# output.net
KiCad netlist of a schematic drawn in EAGLE
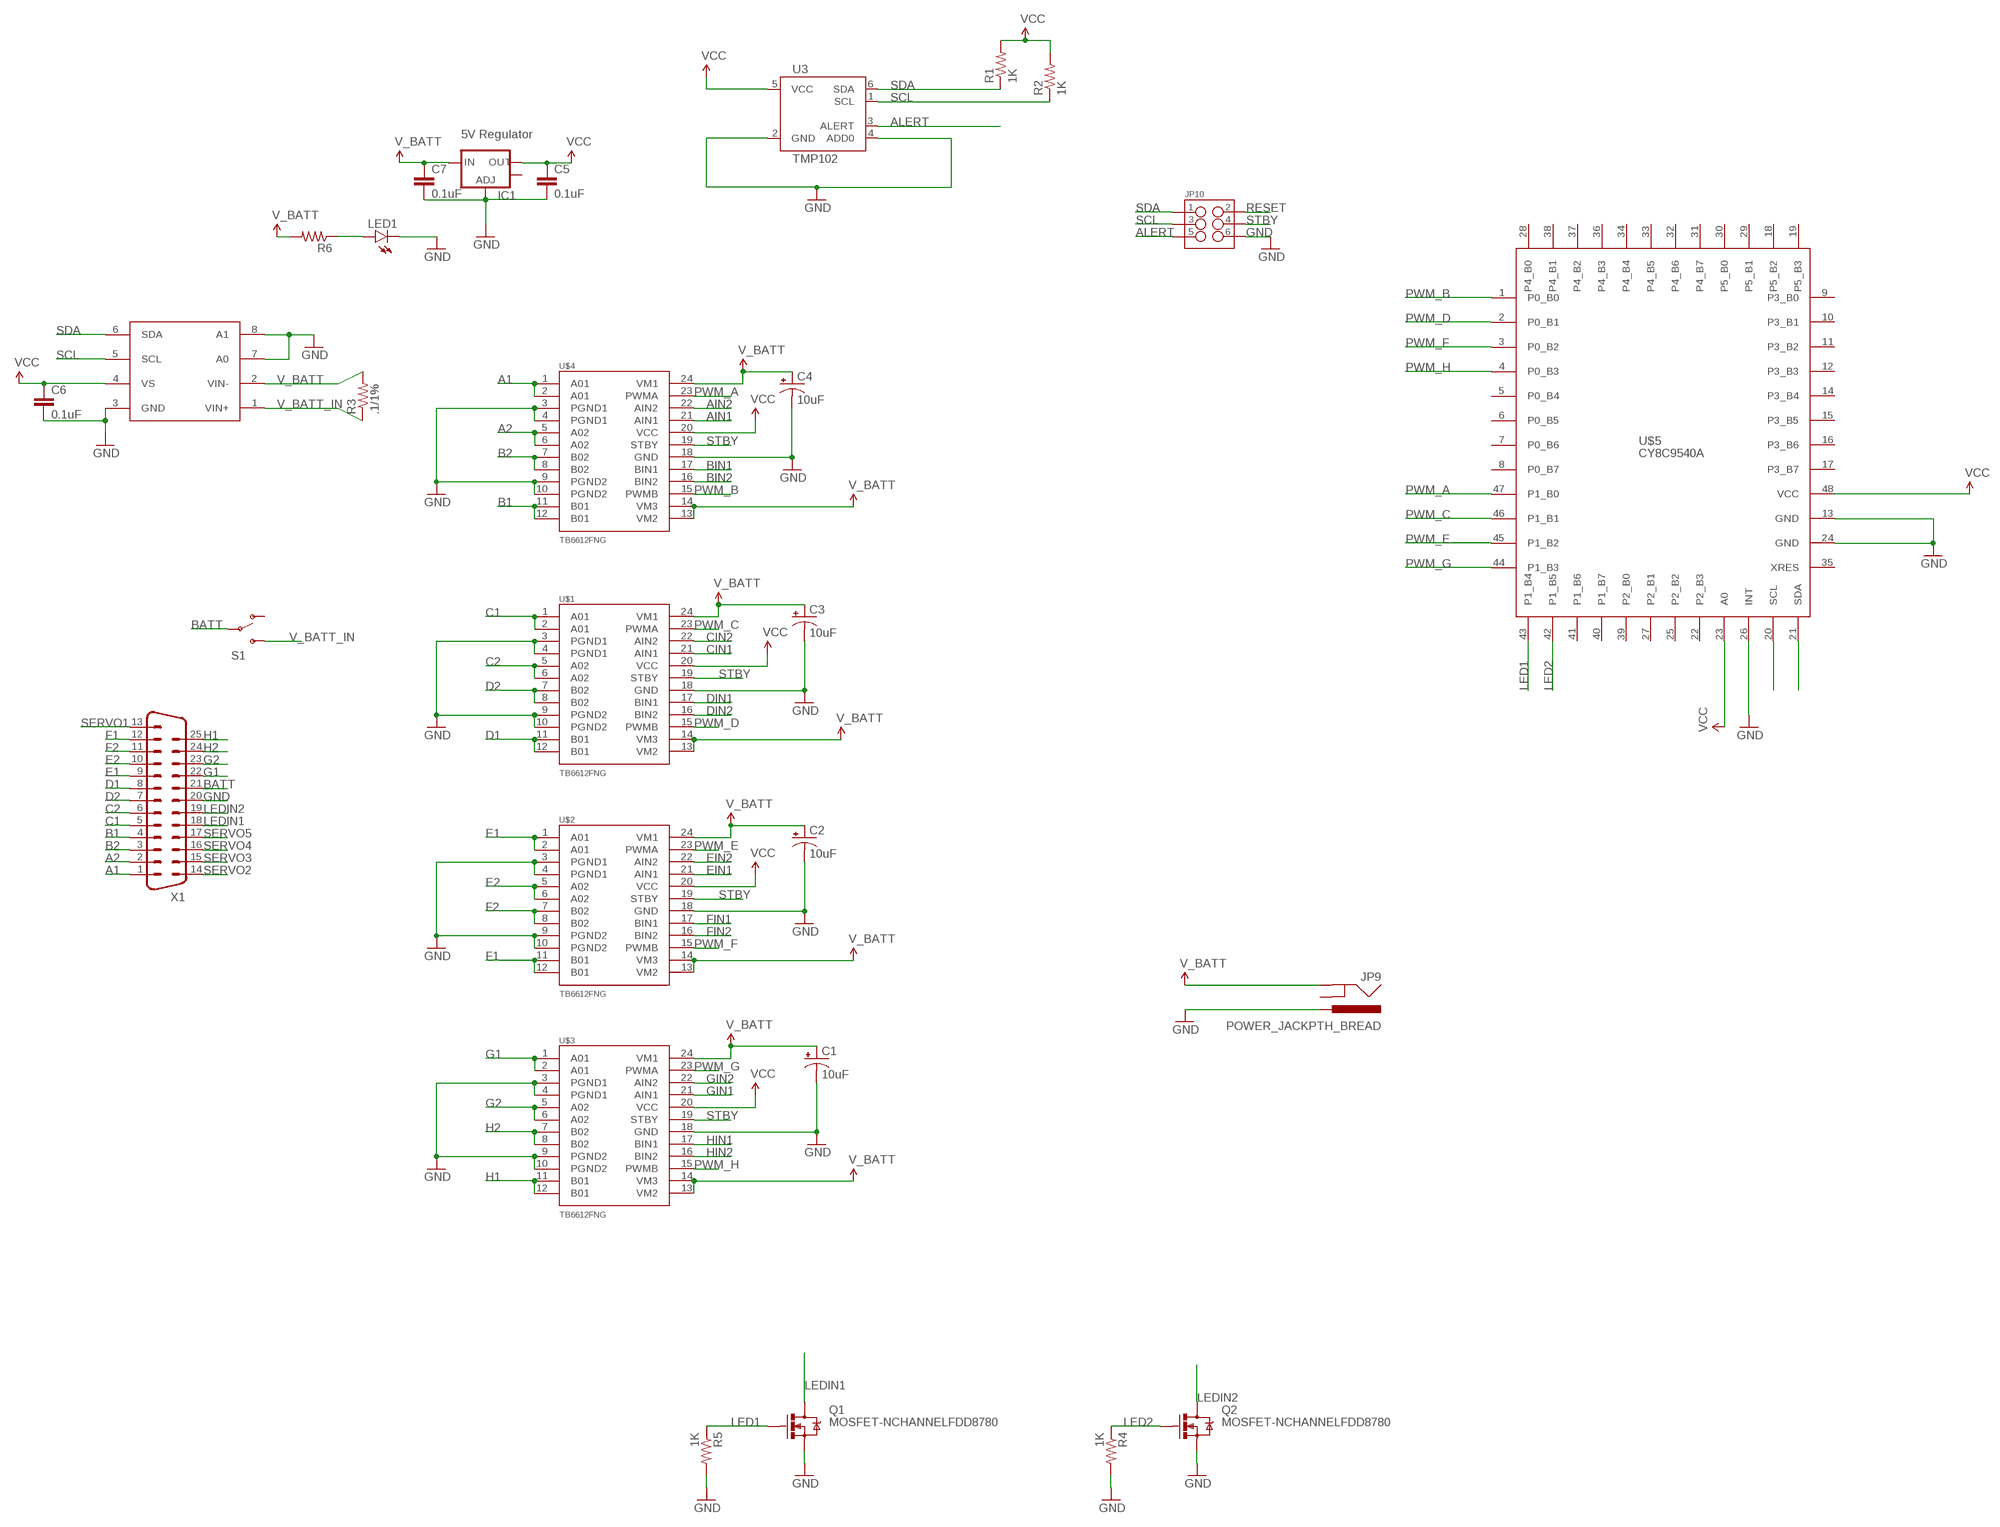
[diagram p0: schematic, sheet 1]

(export (version "E")
  (design (tool "Eeschema 10.0.6"))
  (components
    (comp (ref "C1")
      (value "10uF")
      (footprint "eagle-import:EIA3528")
      (libsource (lib "eagle-import") (part "10UF-20V-10%(TANT)"))
    )
    (comp (ref "C2")
      (value "10uF")
      (footprint "eagle-import:EIA3528")
      (libsource (lib "eagle-import") (part "10UF-20V-10%(TANT)"))
    )
    (comp (ref "C3")
      (value "10uF")
      (footprint "eagle-import:EIA3528")
      (libsource (lib "eagle-import") (part "10UF-20V-10%(TANT)"))
    )
    (comp (ref "C4")
      (value "10uF")
      (footprint "eagle-import:EIA3528")
      (libsource (lib "eagle-import") (part "10UF-20V-10%(TANT)"))
    )
    (comp (ref "C5")
      (value "0.1uF")
      (footprint "eagle-import:0603-CAP")
      (libsource (lib "eagle-import") (part "0.1UF-25V-5%(0603)"))
    )
    (comp (ref "C6")
      (value "0.1uF")
      (footprint "eagle-import:0603-CAP")
      (libsource (lib "eagle-import") (part "0.1UF-25V-5%(0603)"))
    )
    (comp (ref "C7")
      (value "0.1uF")
      (footprint "eagle-import:0603-CAP")
      (libsource (lib "eagle-import") (part "0.1UF-25V-5%(0603)"))
    )
    (comp (ref "IC1")
      (value "V_REG_LM1117SOT223")
      (footprint "eagle-import:SOT223")
      (libsource (lib "eagle-import") (part "V_REG_LM1117SOT223"))
    )
    (comp (ref "JP9")
      (value "POWER_JACKPTH_BREAD")
      (footprint "eagle-import:POWER_JACK_PTH_BREAD")
      (libsource (lib "eagle-import") (part "POWER_JACKPTH_BREAD"))
    )
    (comp (ref "JP10")
      (value "M03X2SHROUD")
      (footprint "eagle-import:2X3-SHROUDED")
      (libsource (lib "eagle-import") (part "M03X2SHROUD"))
    )
    (comp (ref "LED1")
      (value "LED0603")
      (footprint "eagle-import:LED-0603")
      (libsource (lib "eagle-import") (part "LED0603"))
    )
    (comp (ref "Q1")
      (value "MOSFET-NCHANNELFDD8780")
      (footprint "eagle-import:DPAK")
      (libsource (lib "eagle-import") (part "MOSFET-NCHANNELFDD8780"))
    )
    (comp (ref "Q2")
      (value "MOSFET-NCHANNELFDD8780")
      (footprint "eagle-import:DPAK")
      (libsource (lib "eagle-import") (part "MOSFET-NCHANNELFDD8780"))
    )
    (comp (ref "R1")
      (value "1K")
      (footprint "eagle-import:0603-RES")
      (libsource (lib "eagle-import") (part "1KOHM-1/10W-1%(0603)"))
    )
    (comp (ref "R2")
      (value "1K")
      (footprint "eagle-import:0603-RES")
      (libsource (lib "eagle-import") (part "1KOHM-1/10W-1%(0603)"))
    )
    (comp (ref "R3")
      (value ".1/1%")
      (footprint "eagle-import:R2512")
      (libsource (lib "eagle-import") (part "RESISTOR2512"))
    )
    (comp (ref "R4")
      (value "1K")
      (footprint "eagle-import:0603-RES")
      (libsource (lib "eagle-import") (part "1KOHM-1/10W-1%(0603)"))
    )
    (comp (ref "R5")
      (value "1K")
      (footprint "eagle-import:0603-RES")
      (libsource (lib "eagle-import") (part "1KOHM-1/10W-1%(0603)"))
    )
    (comp (ref "R6")
      (value "RESISTOR0603-RES")
      (footprint "eagle-import:0603-RES")
      (libsource (lib "eagle-import") (part "RESISTOR0603-RES"))
    )
    (comp (ref "S1")
      (value "SWITCH-SPDTKIT")
      (footprint "eagle-import:SWITCH-SPDT_KIT")
      (fields (field (name "PARTNO") "EG1218"))
      (libsource (lib "eagle-import") (part "SWITCH-SPDTKIT"))
    )
    (comp (ref "U$1")
      (value "TB6612FNG")
      (footprint "eagle-import:SSOP24")
      (libsource (lib "eagle-import") (part "TB6612FNG"))
    )
    (comp (ref "U$2")
      (value "TB6612FNG")
      (footprint "eagle-import:SSOP24")
      (libsource (lib "eagle-import") (part "TB6612FNG"))
    )
    (comp (ref "U$3")
      (value "TB6612FNG")
      (footprint "eagle-import:SSOP24")
      (libsource (lib "eagle-import") (part "TB6612FNG"))
    )
    (comp (ref "U$4")
      (value "TB6612FNG")
      (footprint "eagle-import:SSOP24")
      (libsource (lib "eagle-import") (part "TB6612FNG"))
    )
    (comp (ref "U$5")
      (value "CY8C9540A")
      (footprint "eagle-import:48-SSOP-CY")
      (libsource (lib "eagle-import") (part "CY8C9540A"))
    )
    (comp (ref "U$6")
      (value "INA219")
      (footprint "eagle-import:SOT23-8")
      (libsource (lib "eagle-import") (part "INA219"))
    )
    (comp (ref "U3")
      (value "TMP102")
      (footprint "eagle-import:SOT563")
      (libsource (lib "eagle-import") (part "TMP102"))
    )
    (comp (ref "X1")
      (value "DB25D")
      (footprint "eagle-import:M25D")
      (libsource (lib "eagle-import") (part "DB25D"))
    )
  )
  (nets
    (net (code "1") (name "/A1") (class "Default")
      (node (ref "U$4") (pin "1") (pinfunction "A01_1") (pintype "bidirectional"))
      (node (ref "U$4") (pin "2") (pinfunction "A01_2") (pintype "bidirectional"))
      (node (ref "X1") (pin "1") (pinfunction "1_1") (pintype "passive"))
    )
    (net (code "2") (name "/A2") (class "Default")
      (node (ref "U$4") (pin "5") (pinfunction "A02_5") (pintype "bidirectional"))
      (node (ref "U$4") (pin "6") (pinfunction "A02_6") (pintype "bidirectional"))
      (node (ref "X1") (pin "2") (pinfunction "2_2") (pintype "passive"))
    )
    (net (code "3") (name "/AIN1") (class "Default")
      (node (ref "U$4") (pin "21") (pinfunction "AIN1_21") (pintype "bidirectional"))
    )
    (net (code "4") (name "/AIN2") (class "Default")
      (node (ref "U$4") (pin "22") (pinfunction "AIN2_22") (pintype "bidirectional"))
    )
    (net (code "5") (name "/ALERT") (class "Default")
      (node (ref "JP10") (pin "5") (pinfunction "5_5") (pintype "bidirectional"))
      (node (ref "U3") (pin "3") (pinfunction "ALERT_3") (pintype "bidirectional"))
    )
    (net (code "6") (name "/B1") (class "Default")
      (node (ref "U$4") (pin "11") (pinfunction "B01_11") (pintype "bidirectional"))
      (node (ref "U$4") (pin "12") (pinfunction "B01_12") (pintype "bidirectional"))
      (node (ref "X1") (pin "4") (pinfunction "4_4") (pintype "passive"))
    )
    (net (code "7") (name "/B2") (class "Default")
      (node (ref "U$4") (pin "7") (pinfunction "B02_7") (pintype "bidirectional"))
      (node (ref "U$4") (pin "8") (pinfunction "B02_8") (pintype "bidirectional"))
      (node (ref "X1") (pin "3") (pinfunction "3_3") (pintype "passive"))
    )
    (net (code "8") (name "/BATT") (class "Default")
      (node (ref "S1") (pin "2") (pinfunction "P_2") (pintype "passive"))
      (node (ref "X1") (pin "21") (pinfunction "21_21") (pintype "passive"))
    )
    (net (code "9") (name "/BIN1") (class "Default")
      (node (ref "U$4") (pin "17") (pinfunction "BIN1_17") (pintype "bidirectional"))
    )
    (net (code "10") (name "/BIN2") (class "Default")
      (node (ref "U$4") (pin "16") (pinfunction "BIN2_16") (pintype "bidirectional"))
    )
    (net (code "11") (name "/C1") (class "Default")
      (node (ref "U$1") (pin "1") (pinfunction "A01_1") (pintype "bidirectional"))
      (node (ref "U$1") (pin "2") (pinfunction "A01_2") (pintype "bidirectional"))
      (node (ref "X1") (pin "5") (pinfunction "5_5") (pintype "passive"))
    )
    (net (code "12") (name "/C2") (class "Default")
      (node (ref "U$1") (pin "5") (pinfunction "A02_5") (pintype "bidirectional"))
      (node (ref "U$1") (pin "6") (pinfunction "A02_6") (pintype "bidirectional"))
      (node (ref "X1") (pin "6") (pinfunction "6_6") (pintype "passive"))
    )
    (net (code "13") (name "/CIN1") (class "Default")
      (node (ref "U$1") (pin "21") (pinfunction "AIN1_21") (pintype "bidirectional"))
    )
    (net (code "14") (name "/CIN2") (class "Default")
      (node (ref "U$1") (pin "22") (pinfunction "AIN2_22") (pintype "bidirectional"))
    )
    (net (code "15") (name "/D1") (class "Default")
      (node (ref "U$1") (pin "11") (pinfunction "B01_11") (pintype "bidirectional"))
      (node (ref "U$1") (pin "12") (pinfunction "B01_12") (pintype "bidirectional"))
      (node (ref "X1") (pin "8") (pinfunction "8_8") (pintype "passive"))
    )
    (net (code "16") (name "/D2") (class "Default")
      (node (ref "U$1") (pin "7") (pinfunction "B02_7") (pintype "bidirectional"))
      (node (ref "U$1") (pin "8") (pinfunction "B02_8") (pintype "bidirectional"))
      (node (ref "X1") (pin "7") (pinfunction "7_7") (pintype "passive"))
    )
    (net (code "17") (name "/DIN1") (class "Default")
      (node (ref "U$1") (pin "17") (pinfunction "BIN1_17") (pintype "bidirectional"))
    )
    (net (code "18") (name "/DIN2") (class "Default")
      (node (ref "U$1") (pin "16") (pinfunction "BIN2_16") (pintype "bidirectional"))
    )
    (net (code "19") (name "/E1") (class "Default")
      (node (ref "U$2") (pin "1") (pinfunction "A01_1") (pintype "bidirectional"))
      (node (ref "U$2") (pin "2") (pinfunction "A01_2") (pintype "bidirectional"))
      (node (ref "X1") (pin "9") (pinfunction "9_9") (pintype "passive"))
    )
    (net (code "20") (name "/E2") (class "Default")
      (node (ref "U$2") (pin "5") (pinfunction "A02_5") (pintype "bidirectional"))
      (node (ref "U$2") (pin "6") (pinfunction "A02_6") (pintype "bidirectional"))
      (node (ref "X1") (pin "10") (pinfunction "10_10") (pintype "passive"))
    )
    (net (code "21") (name "/EIN1") (class "Default")
      (node (ref "U$2") (pin "21") (pinfunction "AIN1_21") (pintype "bidirectional"))
    )
    (net (code "22") (name "/EIN2") (class "Default")
      (node (ref "U$2") (pin "22") (pinfunction "AIN2_22") (pintype "bidirectional"))
    )
    (net (code "23") (name "/F1") (class "Default")
      (node (ref "U$2") (pin "11") (pinfunction "B01_11") (pintype "bidirectional"))
      (node (ref "U$2") (pin "12") (pinfunction "B01_12") (pintype "bidirectional"))
      (node (ref "X1") (pin "12") (pinfunction "12_12") (pintype "passive"))
    )
    (net (code "24") (name "/F2") (class "Default")
      (node (ref "U$2") (pin "7") (pinfunction "B02_7") (pintype "bidirectional"))
      (node (ref "U$2") (pin "8") (pinfunction "B02_8") (pintype "bidirectional"))
      (node (ref "X1") (pin "11") (pinfunction "11_11") (pintype "passive"))
    )
    (net (code "25") (name "/FIN1") (class "Default")
      (node (ref "U$2") (pin "17") (pinfunction "BIN1_17") (pintype "bidirectional"))
    )
    (net (code "26") (name "/FIN2") (class "Default")
      (node (ref "U$2") (pin "16") (pinfunction "BIN2_16") (pintype "bidirectional"))
    )
    (net (code "27") (name "/G1") (class "Default")
      (node (ref "U$3") (pin "1") (pinfunction "A01_1") (pintype "bidirectional"))
      (node (ref "U$3") (pin "2") (pinfunction "A01_2") (pintype "bidirectional"))
      (node (ref "X1") (pin "22") (pinfunction "22_22") (pintype "passive"))
    )
    (net (code "28") (name "/G2") (class "Default")
      (node (ref "U$3") (pin "5") (pinfunction "A02_5") (pintype "bidirectional"))
      (node (ref "U$3") (pin "6") (pinfunction "A02_6") (pintype "bidirectional"))
      (node (ref "X1") (pin "23") (pinfunction "23_23") (pintype "passive"))
    )
    (net (code "29") (name "/GIN1") (class "Default")
      (node (ref "U$3") (pin "21") (pinfunction "AIN1_21") (pintype "bidirectional"))
    )
    (net (code "30") (name "/GIN2") (class "Default")
      (node (ref "U$3") (pin "22") (pinfunction "AIN2_22") (pintype "bidirectional"))
    )
    (net (code "31") (name "/H1") (class "Default")
      (node (ref "U$3") (pin "11") (pinfunction "B01_11") (pintype "bidirectional"))
      (node (ref "U$3") (pin "12") (pinfunction "B01_12") (pintype "bidirectional"))
      (node (ref "X1") (pin "25") (pinfunction "25_25") (pintype "passive"))
    )
    (net (code "32") (name "/H2") (class "Default")
      (node (ref "U$3") (pin "7") (pinfunction "B02_7") (pintype "bidirectional"))
      (node (ref "U$3") (pin "8") (pinfunction "B02_8") (pintype "bidirectional"))
      (node (ref "X1") (pin "24") (pinfunction "24_24") (pintype "passive"))
    )
    (net (code "33") (name "/HIN1") (class "Default")
      (node (ref "U$3") (pin "17") (pinfunction "BIN1_17") (pintype "bidirectional"))
    )
    (net (code "34") (name "/HIN2") (class "Default")
      (node (ref "U$3") (pin "16") (pinfunction "BIN2_16") (pintype "bidirectional"))
    )
    (net (code "35") (name "/LED1") (class "Default")
      (node (ref "Q1") (pin "1") (pinfunction "G_1") (pintype "passive"))
      (node (ref "R5") (pin "1") (pinfunction "1_1") (pintype "passive"))
      (node (ref "U$5") (pin "43") (pinfunction "P1_B4_43") (pintype "bidirectional"))
    )
    (net (code "36") (name "/LED2") (class "Default")
      (node (ref "Q2") (pin "1") (pinfunction "G_1") (pintype "passive"))
      (node (ref "R4") (pin "1") (pinfunction "1_1") (pintype "passive"))
      (node (ref "U$5") (pin "42") (pinfunction "P1_B5_42") (pintype "bidirectional"))
    )
    (net (code "37") (name "/LEDIN1") (class "Default")
      (node (ref "Q1") (pin "4") (pinfunction "D_4") (pintype "passive"))
      (node (ref "X1") (pin "18") (pinfunction "18_18") (pintype "passive"))
    )
    (net (code "38") (name "/LEDIN2") (class "Default")
      (node (ref "Q2") (pin "4") (pinfunction "D_4") (pintype "passive"))
      (node (ref "X1") (pin "19") (pinfunction "19_19") (pintype "passive"))
    )
    (net (code "39") (name "/PWM_A") (class "Default")
      (node (ref "U$4") (pin "23") (pinfunction "PWMA_23") (pintype "bidirectional"))
      (node (ref "U$5") (pin "47") (pinfunction "P1_B0_47") (pintype "bidirectional"))
    )
    (net (code "40") (name "/PWM_B") (class "Default")
      (node (ref "U$4") (pin "15") (pinfunction "PWMB_15") (pintype "bidirectional"))
      (node (ref "U$5") (pin "1") (pinfunction "P0_B0_1") (pintype "bidirectional"))
    )
    (net (code "41") (name "/PWM_C") (class "Default")
      (node (ref "U$1") (pin "23") (pinfunction "PWMA_23") (pintype "bidirectional"))
      (node (ref "U$5") (pin "46") (pinfunction "P1_B1_46") (pintype "bidirectional"))
    )
    (net (code "42") (name "/PWM_D") (class "Default")
      (node (ref "U$1") (pin "15") (pinfunction "PWMB_15") (pintype "bidirectional"))
      (node (ref "U$5") (pin "2") (pinfunction "P0_B1_2") (pintype "bidirectional"))
    )
    (net (code "43") (name "/PWM_E") (class "Default")
      (node (ref "U$2") (pin "23") (pinfunction "PWMA_23") (pintype "bidirectional"))
      (node (ref "U$5") (pin "45") (pinfunction "P1_B2_45") (pintype "bidirectional"))
    )
    (net (code "44") (name "/PWM_F") (class "Default")
      (node (ref "U$2") (pin "15") (pinfunction "PWMB_15") (pintype "bidirectional"))
      (node (ref "U$5") (pin "3") (pinfunction "P0_B2_3") (pintype "bidirectional"))
    )
    (net (code "45") (name "/PWM_G") (class "Default")
      (node (ref "U$3") (pin "23") (pinfunction "PWMA_23") (pintype "bidirectional"))
      (node (ref "U$5") (pin "44") (pinfunction "P1_B3_44") (pintype "bidirectional"))
    )
    (net (code "46") (name "/PWM_H") (class "Default")
      (node (ref "U$3") (pin "15") (pinfunction "PWMB_15") (pintype "bidirectional"))
      (node (ref "U$5") (pin "4") (pinfunction "P0_B3_4") (pintype "bidirectional"))
    )
    (net (code "47") (name "/RESET") (class "Default")
      (node (ref "JP10") (pin "2") (pinfunction "2_2") (pintype "bidirectional"))
    )
    (net (code "48") (name "/SCL") (class "Default")
      (node (ref "JP10") (pin "3") (pinfunction "3_3") (pintype "bidirectional"))
      (node (ref "R2") (pin "1") (pinfunction "1_1") (pintype "passive"))
      (node (ref "U$5") (pin "20") (pinfunction "SCL_20") (pintype "bidirectional"))
      (node (ref "U$6") (pin "5") (pinfunction "SCL_5") (pintype "bidirectional"))
      (node (ref "U3") (pin "1") (pinfunction "SCL_1") (pintype "bidirectional"))
    )
    (net (code "49") (name "/SDA") (class "Default")
      (node (ref "JP10") (pin "1") (pinfunction "1_1") (pintype "bidirectional"))
      (node (ref "R1") (pin "1") (pinfunction "1_1") (pintype "passive"))
      (node (ref "U$5") (pin "21") (pinfunction "SDA_21") (pintype "bidirectional"))
      (node (ref "U$6") (pin "6") (pinfunction "SDA_6") (pintype "bidirectional"))
      (node (ref "U3") (pin "6") (pinfunction "SDA_6") (pintype "bidirectional"))
    )
    (net (code "50") (name "/SERVO1") (class "Default")
      (node (ref "X1") (pin "13") (pinfunction "13_13") (pintype "passive"))
    )
    (net (code "51") (name "/SERVO2") (class "Default")
      (node (ref "X1") (pin "14") (pinfunction "14_14") (pintype "passive"))
    )
    (net (code "52") (name "/SERVO3") (class "Default")
      (node (ref "X1") (pin "15") (pinfunction "15_15") (pintype "passive"))
    )
    (net (code "53") (name "/SERVO4") (class "Default")
      (node (ref "X1") (pin "16") (pinfunction "16_16") (pintype "passive"))
    )
    (net (code "54") (name "/SERVO5") (class "Default")
      (node (ref "X1") (pin "17") (pinfunction "17_17") (pintype "passive"))
    )
    (net (code "55") (name "/STBY") (class "Default")
      (node (ref "JP10") (pin "4") (pinfunction "4_4") (pintype "bidirectional"))
      (node (ref "U$1") (pin "19") (pinfunction "STBY_19") (pintype "bidirectional"))
      (node (ref "U$2") (pin "19") (pinfunction "STBY_19") (pintype "bidirectional"))
      (node (ref "U$3") (pin "19") (pinfunction "STBY_19") (pintype "bidirectional"))
      (node (ref "U$4") (pin "19") (pinfunction "STBY_19") (pintype "bidirectional"))
    )
    (net (code "56") (name "/V_BATT_IN") (class "Default")
      (node (ref "R3") (pin "1") (pinfunction "1_1") (pintype "passive"))
      (node (ref "S1") (pin "3") (pinfunction "S_3") (pintype "passive"))
      (node (ref "U$6") (pin "1") (pinfunction "VIN+_1") (pintype "bidirectional"))
    )
    (net (code "57") (name "GND") (class "Default")
      (node (ref "C1") (pin "C") (pinfunction "-_C") (pintype "passive"))
      (node (ref "C2") (pin "C") (pinfunction "-_C") (pintype "passive"))
      (node (ref "C3") (pin "C") (pinfunction "-_C") (pintype "passive"))
      (node (ref "C4") (pin "C") (pinfunction "-_C") (pintype "passive"))
      (node (ref "C5") (pin "2") (pinfunction "2_2") (pintype "passive"))
      (node (ref "C6") (pin "2") (pinfunction "2_2") (pintype "passive"))
      (node (ref "C7") (pin "2") (pinfunction "2_2") (pintype "passive"))
      (node (ref "IC1") (pin "1") (pinfunction "ADJ_1") (pintype "input"))
      (node (ref "JP10") (pin "6") (pinfunction "6_6") (pintype "bidirectional"))
      (node (ref "JP9") (pin "PWR") (pinfunction "PWR_PWR") (pintype "bidirectional"))
      (node (ref "LED1") (pin "C") (pinfunction "C_C") (pintype "passive"))
      (node (ref "Q1") (pin "3") (pinfunction "S_3") (pintype "passive"))
      (node (ref "Q2") (pin "3") (pinfunction "S_3") (pintype "passive"))
      (node (ref "R4") (pin "2") (pinfunction "2_2") (pintype "passive"))
      (node (ref "R5") (pin "2") (pinfunction "2_2") (pintype "passive"))
      (node (ref "U$1") (pin "10") (pinfunction "PGND2_10") (pintype "bidirectional"))
      (node (ref "U$1") (pin "18") (pinfunction "GND_18") (pintype "bidirectional"))
      (node (ref "U$1") (pin "3") (pinfunction "PGND1_3") (pintype "bidirectional"))
      (node (ref "U$1") (pin "4") (pinfunction "PGND1_4") (pintype "bidirectional"))
      (node (ref "U$1") (pin "9") (pinfunction "PGND2_9") (pintype "bidirectional"))
      (node (ref "U$2") (pin "10") (pinfunction "PGND2_10") (pintype "bidirectional"))
      (node (ref "U$2") (pin "18") (pinfunction "GND_18") (pintype "bidirectional"))
      (node (ref "U$2") (pin "3") (pinfunction "PGND1_3") (pintype "bidirectional"))
      (node (ref "U$2") (pin "4") (pinfunction "PGND1_4") (pintype "bidirectional"))
      (node (ref "U$2") (pin "9") (pinfunction "PGND2_9") (pintype "bidirectional"))
      (node (ref "U$3") (pin "10") (pinfunction "PGND2_10") (pintype "bidirectional"))
      (node (ref "U$3") (pin "18") (pinfunction "GND_18") (pintype "bidirectional"))
      (node (ref "U$3") (pin "3") (pinfunction "PGND1_3") (pintype "bidirectional"))
      (node (ref "U$3") (pin "4") (pinfunction "PGND1_4") (pintype "bidirectional"))
      (node (ref "U$3") (pin "9") (pinfunction "PGND2_9") (pintype "bidirectional"))
      (node (ref "U$4") (pin "10") (pinfunction "PGND2_10") (pintype "bidirectional"))
      (node (ref "U$4") (pin "18") (pinfunction "GND_18") (pintype "bidirectional"))
      (node (ref "U$4") (pin "3") (pinfunction "PGND1_3") (pintype "bidirectional"))
      (node (ref "U$4") (pin "4") (pinfunction "PGND1_4") (pintype "bidirectional"))
      (node (ref "U$4") (pin "9") (pinfunction "PGND2_9") (pintype "bidirectional"))
      (node (ref "U$5") (pin "13") (pinfunction "GND_13") (pintype "bidirectional"))
      (node (ref "U$5") (pin "24") (pinfunction "GND_24") (pintype "bidirectional"))
      (node (ref "U$5") (pin "26") (pinfunction "INT_26") (pintype "bidirectional"))
      (node (ref "U$6") (pin "3") (pinfunction "GND_3") (pintype "bidirectional"))
      (node (ref "U$6") (pin "7") (pinfunction "A0_7") (pintype "bidirectional"))
      (node (ref "U$6") (pin "8") (pinfunction "A1_8") (pintype "bidirectional"))
      (node (ref "U3") (pin "2") (pinfunction "GND_2") (pintype "bidirectional"))
      (node (ref "U3") (pin "4") (pinfunction "ADD0_4") (pintype "bidirectional"))
      (node (ref "X1") (pin "20") (pinfunction "20_20") (pintype "passive"))
    )
    (net (code "58") (name "Net-(LED1-PadA)") (class "Default")
      (node (ref "LED1") (pin "A") (pinfunction "A_A") (pintype "passive"))
      (node (ref "R6") (pin "1") (pinfunction "1_1") (pintype "passive"))
    )
    (net (code "59") (name "VCC") (class "Default")
      (node (ref "C5") (pin "1") (pinfunction "1_1") (pintype "passive"))
      (node (ref "C6") (pin "1") (pinfunction "1_1") (pintype "passive"))
      (node (ref "IC1") (pin "2") (pinfunction "OUT_2") (pintype "output"))
      (node (ref "R1") (pin "2") (pinfunction "2_2") (pintype "passive"))
      (node (ref "R2") (pin "2") (pinfunction "2_2") (pintype "passive"))
      (node (ref "U$1") (pin "20") (pinfunction "VCC_20") (pintype "bidirectional"))
      (node (ref "U$2") (pin "20") (pinfunction "VCC_20") (pintype "bidirectional"))
      (node (ref "U$3") (pin "20") (pinfunction "VCC_20") (pintype "bidirectional"))
      (node (ref "U$4") (pin "20") (pinfunction "VCC_20") (pintype "bidirectional"))
      (node (ref "U$5") (pin "23") (pinfunction "A0_23") (pintype "bidirectional"))
      (node (ref "U$5") (pin "48") (pinfunction "VCC_48") (pintype "bidirectional"))
      (node (ref "U$6") (pin "4") (pinfunction "VS_4") (pintype "bidirectional"))
      (node (ref "U3") (pin "5") (pinfunction "VCC_5") (pintype "bidirectional"))
    )
    (net (code "60") (name "V_BATT") (class "Default")
      (node (ref "C1") (pin "A") (pinfunction "+_A") (pintype "passive"))
      (node (ref "C2") (pin "A") (pinfunction "+_A") (pintype "passive"))
      (node (ref "C3") (pin "A") (pinfunction "+_A") (pintype "passive"))
      (node (ref "C4") (pin "A") (pinfunction "+_A") (pintype "passive"))
      (node (ref "C7") (pin "1") (pinfunction "1_1") (pintype "passive"))
      (node (ref "IC1") (pin "3") (pinfunction "IN_3") (pintype "input"))
      (node (ref "JP9") (pin "GND") (pinfunction "GND_GND") (pintype "bidirectional"))
      (node (ref "R3") (pin "2") (pinfunction "2_2") (pintype "passive"))
      (node (ref "R6") (pin "2") (pinfunction "2_2") (pintype "passive"))
      (node (ref "U$1") (pin "13") (pinfunction "VM2_13") (pintype "bidirectional"))
      (node (ref "U$1") (pin "14") (pinfunction "VM3_14") (pintype "bidirectional"))
      (node (ref "U$1") (pin "24") (pinfunction "VM1_24") (pintype "bidirectional"))
      (node (ref "U$2") (pin "13") (pinfunction "VM2_13") (pintype "bidirectional"))
      (node (ref "U$2") (pin "14") (pinfunction "VM3_14") (pintype "bidirectional"))
      (node (ref "U$2") (pin "24") (pinfunction "VM1_24") (pintype "bidirectional"))
      (node (ref "U$3") (pin "13") (pinfunction "VM2_13") (pintype "bidirectional"))
      (node (ref "U$3") (pin "14") (pinfunction "VM3_14") (pintype "bidirectional"))
      (node (ref "U$3") (pin "24") (pinfunction "VM1_24") (pintype "bidirectional"))
      (node (ref "U$4") (pin "13") (pinfunction "VM2_13") (pintype "bidirectional"))
      (node (ref "U$4") (pin "14") (pinfunction "VM3_14") (pintype "bidirectional"))
      (node (ref "U$4") (pin "24") (pinfunction "VM1_24") (pintype "bidirectional"))
      (node (ref "U$6") (pin "2") (pinfunction "VIN-_2") (pintype "bidirectional"))
    )
    (net (code "61") (name "unconnected-(IC1-OUT-Pad4)") (class "Default")
      (node (ref "IC1") (pin "4") (pinfunction "OUT_4") (pintype "output"))
    )
    (net (code "62") (name "unconnected-(JP9-PadGNDBREAK)") (class "Default")
      (node (ref "JP9") (pin "GNDBREAK") (pinfunction "GNDBREAK_GNDBREAK") (pintype "bidirectional"))
    )
    (net (code "63") (name "unconnected-(S1-O-Pad1)") (class "Default")
      (node (ref "S1") (pin "1") (pinfunction "O_1") (pintype "passive"))
    )
    (net (code "64") (name "unconnected-(U$5-P0_B4-Pad5)") (class "Default")
      (node (ref "U$5") (pin "5") (pinfunction "P0_B4_5") (pintype "bidirectional"))
    )
    (net (code "65") (name "unconnected-(U$5-P0_B5-Pad6)") (class "Default")
      (node (ref "U$5") (pin "6") (pinfunction "P0_B5_6") (pintype "bidirectional"))
    )
    (net (code "66") (name "unconnected-(U$5-P0_B6-Pad7)") (class "Default")
      (node (ref "U$5") (pin "7") (pinfunction "P0_B6_7") (pintype "bidirectional"))
    )
    (net (code "67") (name "unconnected-(U$5-P0_B7-Pad8)") (class "Default")
      (node (ref "U$5") (pin "8") (pinfunction "P0_B7_8") (pintype "bidirectional"))
    )
    (net (code "68") (name "unconnected-(U$5-P1_B6-Pad41)") (class "Default")
      (node (ref "U$5") (pin "41") (pinfunction "P1_B6_41") (pintype "bidirectional"))
    )
    (net (code "69") (name "unconnected-(U$5-P1_B7-Pad40)") (class "Default")
      (node (ref "U$5") (pin "40") (pinfunction "P1_B7_40") (pintype "bidirectional"))
    )
    (net (code "70") (name "unconnected-(U$5-P2_B0-Pad39)") (class "Default")
      (node (ref "U$5") (pin "39") (pinfunction "P2_B0_39") (pintype "bidirectional"))
    )
    (net (code "71") (name "unconnected-(U$5-P2_B1-Pad27)") (class "Default")
      (node (ref "U$5") (pin "27") (pinfunction "P2_B1_27") (pintype "bidirectional"))
    )
    (net (code "72") (name "unconnected-(U$5-P2_B2-Pad25)") (class "Default")
      (node (ref "U$5") (pin "25") (pinfunction "P2_B2_25") (pintype "bidirectional"))
    )
    (net (code "73") (name "unconnected-(U$5-P2_B3-Pad22)") (class "Default")
      (node (ref "U$5") (pin "22") (pinfunction "P2_B3_22") (pintype "bidirectional"))
    )
    (net (code "74") (name "unconnected-(U$5-P3_B0-Pad9)") (class "Default")
      (node (ref "U$5") (pin "9") (pinfunction "P3_B0_9") (pintype "bidirectional"))
    )
    (net (code "75") (name "unconnected-(U$5-P3_B1-Pad10)") (class "Default")
      (node (ref "U$5") (pin "10") (pinfunction "P3_B1_10") (pintype "bidirectional"))
    )
    (net (code "76") (name "unconnected-(U$5-P3_B2-Pad11)") (class "Default")
      (node (ref "U$5") (pin "11") (pinfunction "P3_B2_11") (pintype "bidirectional"))
    )
    (net (code "77") (name "unconnected-(U$5-P3_B3-Pad12)") (class "Default")
      (node (ref "U$5") (pin "12") (pinfunction "P3_B3_12") (pintype "bidirectional"))
    )
    (net (code "78") (name "unconnected-(U$5-P3_B4-Pad14)") (class "Default")
      (node (ref "U$5") (pin "14") (pinfunction "P3_B4_14") (pintype "bidirectional"))
    )
    (net (code "79") (name "unconnected-(U$5-P3_B5-Pad15)") (class "Default")
      (node (ref "U$5") (pin "15") (pinfunction "P3_B5_15") (pintype "bidirectional"))
    )
    (net (code "80") (name "unconnected-(U$5-P3_B6-Pad16)") (class "Default")
      (node (ref "U$5") (pin "16") (pinfunction "P3_B6_16") (pintype "bidirectional"))
    )
    (net (code "81") (name "unconnected-(U$5-P3_B7-Pad17)") (class "Default")
      (node (ref "U$5") (pin "17") (pinfunction "P3_B7_17") (pintype "bidirectional"))
    )
    (net (code "82") (name "unconnected-(U$5-P4_B0-Pad28)") (class "Default")
      (node (ref "U$5") (pin "28") (pinfunction "P4_B0_28") (pintype "bidirectional"))
    )
    (net (code "83") (name "unconnected-(U$5-P4_B1-Pad38)") (class "Default")
      (node (ref "U$5") (pin "38") (pinfunction "P4_B1_38") (pintype "bidirectional"))
    )
    (net (code "84") (name "unconnected-(U$5-P4_B2-Pad37)") (class "Default")
      (node (ref "U$5") (pin "37") (pinfunction "P4_B2_37") (pintype "bidirectional"))
    )
    (net (code "85") (name "unconnected-(U$5-P4_B3-Pad36)") (class "Default")
      (node (ref "U$5") (pin "36") (pinfunction "P4_B3_36") (pintype "bidirectional"))
    )
    (net (code "86") (name "unconnected-(U$5-P4_B4-Pad34)") (class "Default")
      (node (ref "U$5") (pin "34") (pinfunction "P4_B4_34") (pintype "bidirectional"))
    )
    (net (code "87") (name "unconnected-(U$5-P4_B5-Pad33)") (class "Default")
      (node (ref "U$5") (pin "33") (pinfunction "P4_B5_33") (pintype "bidirectional"))
    )
    (net (code "88") (name "unconnected-(U$5-P4_B6-Pad32)") (class "Default")
      (node (ref "U$5") (pin "32") (pinfunction "P4_B6_32") (pintype "bidirectional"))
    )
    (net (code "89") (name "unconnected-(U$5-P4_B7-Pad31)") (class "Default")
      (node (ref "U$5") (pin "31") (pinfunction "P4_B7_31") (pintype "bidirectional"))
    )
    (net (code "90") (name "unconnected-(U$5-P5_B0-Pad30)") (class "Default")
      (node (ref "U$5") (pin "30") (pinfunction "P5_B0_30") (pintype "bidirectional"))
    )
    (net (code "91") (name "unconnected-(U$5-P5_B1-Pad29)") (class "Default")
      (node (ref "U$5") (pin "29") (pinfunction "P5_B1_29") (pintype "bidirectional"))
    )
    (net (code "92") (name "unconnected-(U$5-P5_B2-Pad18)") (class "Default")
      (node (ref "U$5") (pin "18") (pinfunction "P5_B2_18") (pintype "bidirectional"))
    )
    (net (code "93") (name "unconnected-(U$5-P5_B3-Pad19)") (class "Default")
      (node (ref "U$5") (pin "19") (pinfunction "P5_B3_19") (pintype "bidirectional"))
    )
    (net (code "94") (name "unconnected-(U$5-XRES-Pad35)") (class "Default")
      (node (ref "U$5") (pin "35") (pinfunction "XRES_35") (pintype "bidirectional"))
    )
  )
)
